# P2N-002.net
KiCad netlist of a schematic drawn in EAGLE
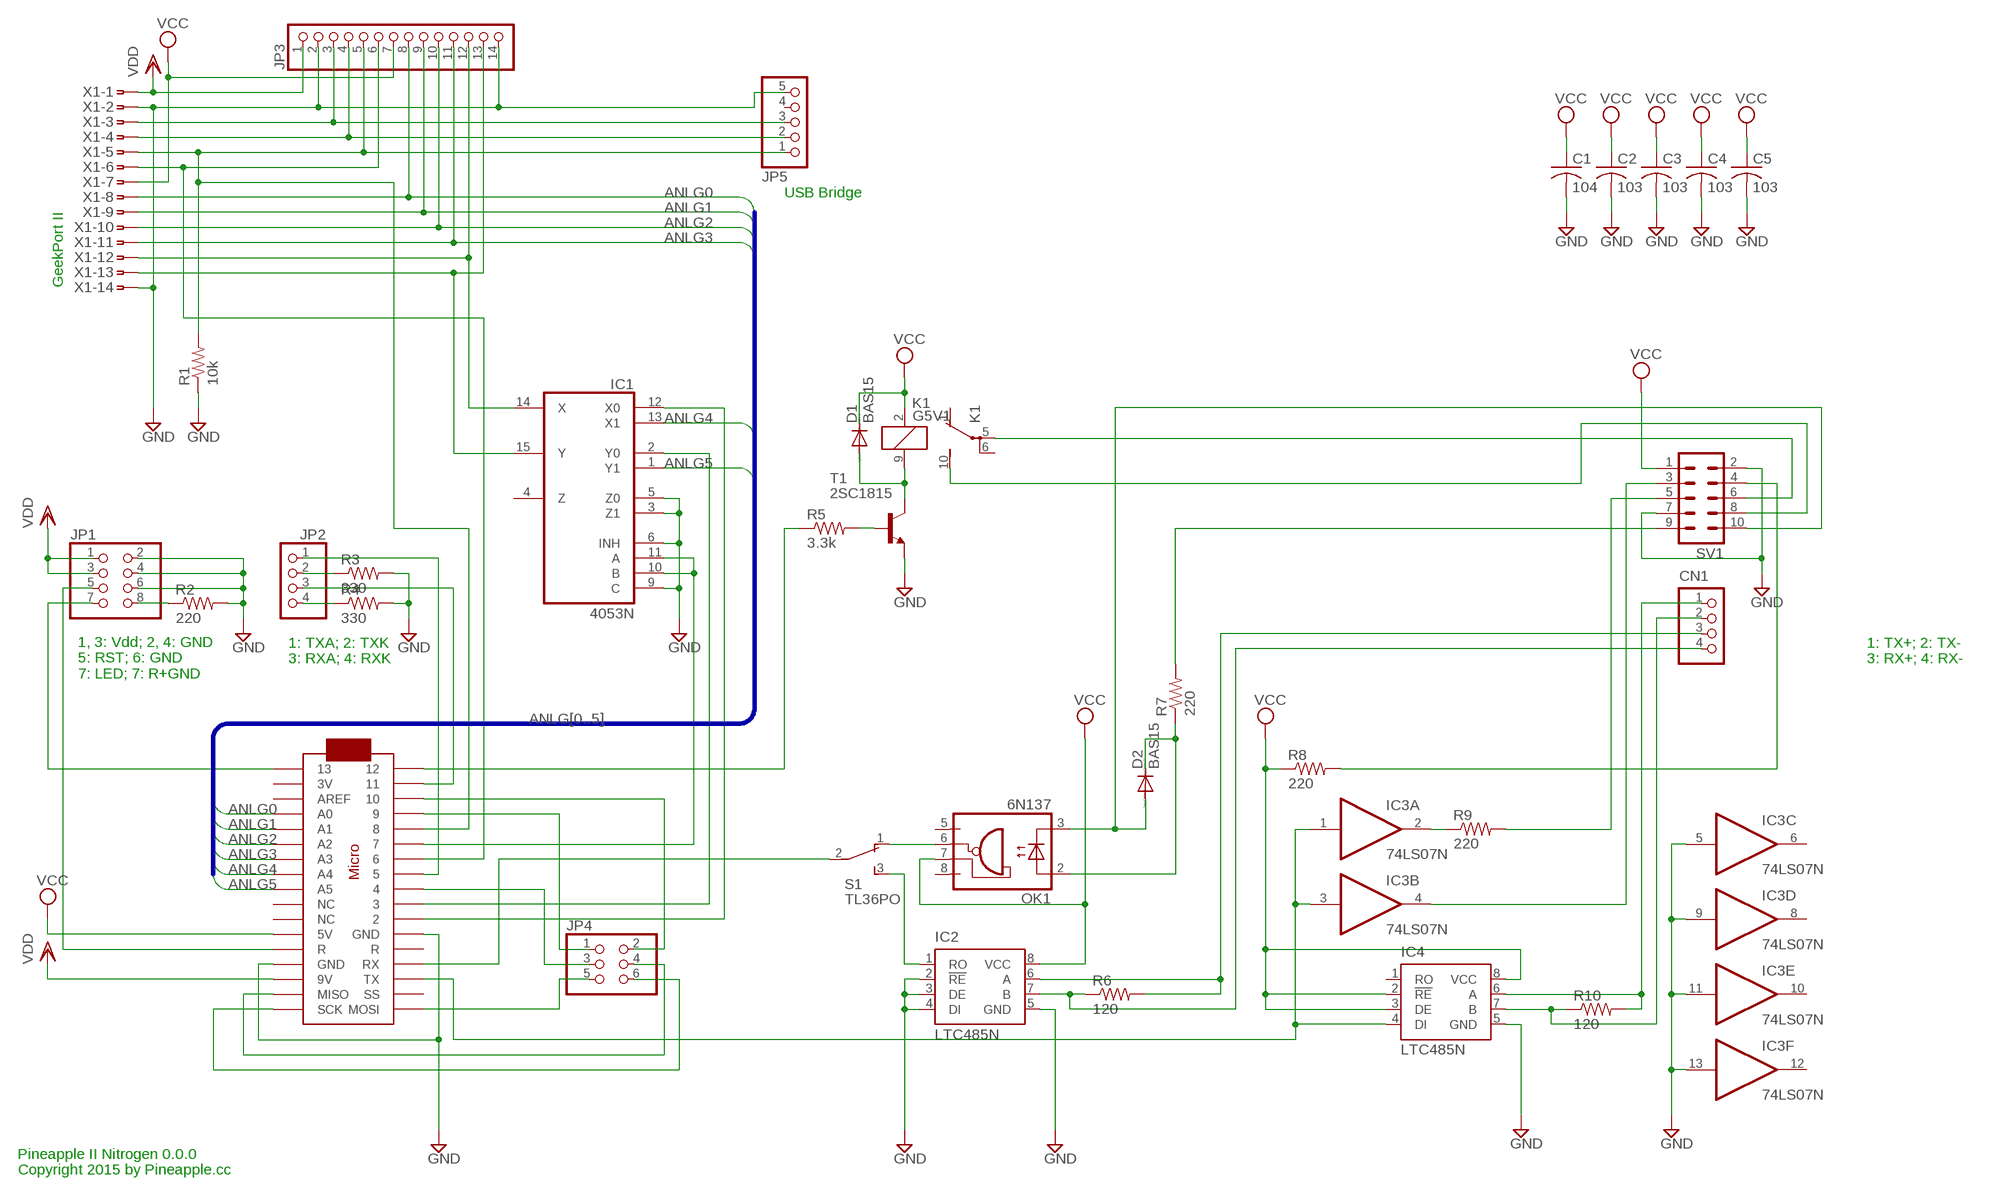
[diagram p0: schematic, sheet 1]

(export (version "E")
  (design (tool "Eeschema 10.0.6"))
  (components
    (comp (ref "C1")
      (value "104")
      (footprint "eagle-import:C025-025X050")
      (libsource (lib "eagle-import") (part "C-US025-025X050"))
    )
    (comp (ref "C2")
      (value "103")
      (footprint "eagle-import:C025-025X050")
      (libsource (lib "eagle-import") (part "C-US025-025X050"))
    )
    (comp (ref "C3")
      (value "103")
      (footprint "eagle-import:C025-025X050")
      (libsource (lib "eagle-import") (part "C-US025-025X050"))
    )
    (comp (ref "C4")
      (value "103")
      (footprint "eagle-import:C025-025X050")
      (libsource (lib "eagle-import") (part "C-US025-025X050"))
    )
    (comp (ref "C5")
      (value "103")
      (footprint "eagle-import:C025-025X050")
      (libsource (lib "eagle-import") (part "C-US025-025X050"))
    )
    (comp (ref "CN1")
      (value "S4B-PH-K-S")
      (footprint "eagle-import:S4B-PH-K-S")
      (libsource (lib "eagle-import") (part "S4B-PH-K-S"))
    )
    (comp (ref "D1")
      (value "BAS15")
      (footprint "eagle-import:DO34-7")
      (libsource (lib "eagle-import") (part "BAS15"))
    )
    (comp (ref "D2")
      (value "BAS15")
      (footprint "eagle-import:DO34-7")
      (libsource (lib "eagle-import") (part "BAS15"))
    )
    (comp (ref "IC1")
      (value "4053N")
      (footprint "eagle-import:DIL16")
      (libsource (lib "eagle-import") (part "4053N"))
    )
    (comp (ref "IC2")
      (value "LTC485N")
      (footprint "eagle-import:DIL08")
      (libsource (lib "eagle-import") (part "LTC485N"))
    )
    (comp (ref "IC3")
      (value "74LS07N")
      (footprint "eagle-import:DIL14")
      (libsource (lib "eagle-import") (part "7407NLS"))
    )
    (comp (ref "IC4")
      (value "LTC485N")
      (footprint "eagle-import:DIL08")
      (libsource (lib "eagle-import") (part "LTC485N"))
    )
    (comp (ref "JP1")
      (value "PINHD-2X4")
      (footprint "eagle-import:2X04")
      (libsource (lib "eagle-import") (part "PINHD-2X4"))
    )
    (comp (ref "JP2")
      (value "PINHD-1X4")
      (footprint "eagle-import:1X04")
      (libsource (lib "eagle-import") (part "PINHD-1X4"))
    )
    (comp (ref "JP3")
      (value "PINHD-1X14")
      (footprint "eagle-import:1X14")
      (libsource (lib "eagle-import") (part "PINHD-1X14"))
    )
    (comp (ref "JP4")
      (value "PINHD-2X3")
      (footprint "eagle-import:2X03")
      (libsource (lib "eagle-import") (part "PINHD-2X3"))
    )
    (comp (ref "JP5")
      (value "PINHD-1X5/90")
      (footprint "eagle-import:1X05_90")
      (libsource (lib "eagle-import") (part "PINHD-1X5/90"))
    )
    (comp (ref "K1")
      (value "G5V1")
      (footprint "eagle-import:G5V1")
      (fields (field (name "MPN") "G5V-1-DC24"))
      (libsource (lib "eagle-import") (part "G5V1"))
    )
    (comp (ref "MC1")
      (value "ARDUINOMICRO")
      (footprint "eagle-import:ARDUINOMICRO")
      (libsource (lib "eagle-import") (part "ARDUINOMICRO"))
    )
    (comp (ref "OK1")
      (value "6N137")
      (footprint "eagle-import:DIL08")
      (libsource (lib "eagle-import") (part "6N137"))
    )
    (comp (ref "R1")
      (value "10k")
      (footprint "eagle-import:0204_5")
      (libsource (lib "eagle-import") (part "R-US_0204/5"))
    )
    (comp (ref "R2")
      (value "220")
      (footprint "eagle-import:0204_5")
      (libsource (lib "eagle-import") (part "R-US_0204/5"))
    )
    (comp (ref "R3")
      (value "330")
      (footprint "eagle-import:0204_5")
      (libsource (lib "eagle-import") (part "R-US_0204/5"))
    )
    (comp (ref "R4")
      (value "330")
      (footprint "eagle-import:0204_5")
      (libsource (lib "eagle-import") (part "R-US_0204/5"))
    )
    (comp (ref "R5")
      (value "3.3k")
      (footprint "eagle-import:0204_5")
      (libsource (lib "eagle-import") (part "R-US_0204/5"))
    )
    (comp (ref "R6")
      (value "120")
      (footprint "eagle-import:0204_5")
      (libsource (lib "eagle-import") (part "R-US_0204/5"))
    )
    (comp (ref "R7")
      (value "220")
      (footprint "eagle-import:0204_5")
      (libsource (lib "eagle-import") (part "R-US_0204/5"))
    )
    (comp (ref "R8")
      (value "220")
      (footprint "eagle-import:0204_5")
      (libsource (lib "eagle-import") (part "R-US_0204/5"))
    )
    (comp (ref "R9")
      (value "220")
      (footprint "eagle-import:0204_5")
      (libsource (lib "eagle-import") (part "R-US_0204/5"))
    )
    (comp (ref "R10")
      (value "120")
      (footprint "eagle-import:0204_5")
      (libsource (lib "eagle-import") (part "R-US_0204/5"))
    )
    (comp (ref "S1")
      (value "TL36PO")
      (footprint "eagle-import:TL3XPO")
      (libsource (lib "eagle-import") (part "TL36PO"))
    )
    (comp (ref "SV1")
      (value "ML10L")
      (footprint "eagle-import:ML10L")
      (libsource (lib "eagle-import") (part "ML10L"))
    )
    (comp (ref "T1")
      (value "2SC1815")
      (footprint "eagle-import:TO92-ECB")
      (libsource (lib "eagle-import") (part "2SC1815"))
    )
    (comp (ref "X1")
      (value "HIROSE-DXLM")
      (footprint "eagle-import:HIROSE-DXLM")
      (libsource (lib "eagle-import") (part "HIROSE-DXLM"))
    )
  )
  (nets
    (net (code "1") (name "/ANLG0") (class "Default")
      (node (ref "JP3") (pin "8") (pinfunction "8_8") (pintype "passive"))
      (node (ref "MC1") (pin "P$31") (pinfunction "A0_P$31") (pintype "bidirectional"))
      (node (ref "X1") (pin "8") (pinfunction "1_8") (pintype "passive"))
    )
    (net (code "2") (name "/ANLG1") (class "Default")
      (node (ref "JP3") (pin "9") (pinfunction "9_9") (pintype "passive"))
      (node (ref "MC1") (pin "P$30") (pinfunction "A1_P$30") (pintype "bidirectional"))
      (node (ref "X1") (pin "9") (pinfunction "1_9") (pintype "passive"))
    )
    (net (code "3") (name "/ANLG2") (class "Default")
      (node (ref "JP3") (pin "10") (pinfunction "10_10") (pintype "passive"))
      (node (ref "MC1") (pin "P$29") (pinfunction "A2_P$29") (pintype "bidirectional"))
      (node (ref "X1") (pin "10") (pinfunction "1_10") (pintype "passive"))
    )
    (net (code "4") (name "/ANLG3") (class "Default")
      (node (ref "JP3") (pin "11") (pinfunction "11_11") (pintype "passive"))
      (node (ref "MC1") (pin "P$28") (pinfunction "A3_P$28") (pintype "bidirectional"))
      (node (ref "X1") (pin "11") (pinfunction "1_11") (pintype "passive"))
    )
    (net (code "5") (name "/ANLG4") (class "Default")
      (node (ref "IC1") (pin "13") (pinfunction "X1_13") (pintype "bidirectional"))
      (node (ref "MC1") (pin "P$27") (pinfunction "A4_P$27") (pintype "bidirectional"))
    )
    (net (code "6") (name "/ANLG5") (class "Default")
      (node (ref "IC1") (pin "1") (pinfunction "Y1_1") (pintype "bidirectional"))
      (node (ref "MC1") (pin "P$26") (pinfunction "A5_P$26") (pintype "bidirectional"))
    )
    (net (code "8") (name "GND") (class "Default")
      (node (ref "C1") (pin "2") (pinfunction "2_2") (pintype "passive"))
      (node (ref "C2") (pin "2") (pinfunction "2_2") (pintype "passive"))
      (node (ref "C3") (pin "2") (pinfunction "2_2") (pintype "passive"))
      (node (ref "C4") (pin "2") (pinfunction "2_2") (pintype "passive"))
      (node (ref "C5") (pin "2") (pinfunction "2_2") (pintype "passive"))
      (node (ref "IC1") (pin "3") (pinfunction "Z1_3") (pintype "bidirectional"))
      (node (ref "IC1") (pin "5") (pinfunction "Z0_5") (pintype "bidirectional"))
      (node (ref "IC1") (pin "6") (pinfunction "INH_6") (pintype "input"))
      (node (ref "IC1") (pin "9") (pinfunction "C_9") (pintype "input"))
      (node (ref "IC2") (pin "2") (pinfunction "~{RE}_2") (pintype "input"))
      (node (ref "IC2") (pin "3") (pinfunction "DE_3") (pintype "input"))
      (node (ref "IC2") (pin "4") (pinfunction "DI_4") (pintype "input"))
      (node (ref "IC2") (pin "5") (pinfunction "GND_5") (pintype "input"))
      (node (ref "IC3") (pin "11") (pinfunction "I_11") (pintype "input"))
      (node (ref "IC3") (pin "13") (pinfunction "I_13") (pintype "input"))
      (node (ref "IC3") (pin "5") (pinfunction "I_5") (pintype "input"))
      (node (ref "IC3") (pin "9") (pinfunction "I_9") (pintype "input"))
      (node (ref "IC4") (pin "5") (pinfunction "GND_5") (pintype "input"))
      (node (ref "JP1") (pin "2") (pinfunction "2_2") (pintype "passive"))
      (node (ref "JP1") (pin "4") (pinfunction "4_4") (pintype "passive"))
      (node (ref "JP1") (pin "6") (pinfunction "6_6") (pintype "passive"))
      (node (ref "JP3") (pin "14") (pinfunction "14_14") (pintype "passive"))
      (node (ref "JP3") (pin "2") (pinfunction "2_2") (pintype "passive"))
      (node (ref "JP5") (pin "5") (pinfunction "5_5") (pintype "passive"))
      (node (ref "MC1") (pin "P$12") (pinfunction "GND_P$12") (pintype "bidirectional"))
      (node (ref "MC1") (pin "P$21") (pinfunction "GND_P$21") (pintype "bidirectional"))
      (node (ref "R1") (pin "1") (pinfunction "1_1") (pintype "passive"))
      (node (ref "R2") (pin "2") (pinfunction "2_2") (pintype "passive"))
      (node (ref "R3") (pin "2") (pinfunction "2_2") (pintype "passive"))
      (node (ref "R4") (pin "2") (pinfunction "2_2") (pintype "passive"))
      (node (ref "SV1") (pin "2") (pinfunction "2_2") (pintype "passive"))
      (node (ref "SV1") (pin "7") (pinfunction "7_7") (pintype "passive"))
      (node (ref "T1") (pin "E") (pinfunction "E_E") (pintype "passive"))
      (node (ref "X1") (pin "14") (pinfunction "1_14") (pintype "passive"))
      (node (ref "X1") (pin "2") (pinfunction "1_2") (pintype "passive"))
    )
    (net (code "9") (name "Net-(IC1A-A)") (class "Default")
      (node (ref "IC1") (pin "10") (pinfunction "B_10") (pintype "input"))
      (node (ref "IC1") (pin "11") (pinfunction "A_11") (pintype "input"))
      (node (ref "MC1") (pin "P$6") (pinfunction "7_P$6") (pintype "bidirectional"))
    )
    (net (code "10") (name "Net-(IC1A-X)") (class "Default")
      (node (ref "IC1") (pin "14") (pinfunction "X_14") (pintype "bidirectional"))
      (node (ref "JP3") (pin "12") (pinfunction "12_12") (pintype "passive"))
      (node (ref "X1") (pin "12") (pinfunction "1_12") (pintype "passive"))
    )
    (net (code "11") (name "Net-(IC1A-X0)") (class "Default")
      (node (ref "IC1") (pin "12") (pinfunction "X0_12") (pintype "bidirectional"))
      (node (ref "MC1") (pin "P$11") (pinfunction "2_P$11") (pintype "bidirectional"))
    )
    (net (code "12") (name "Net-(IC1A-Y)") (class "Default")
      (node (ref "IC1") (pin "15") (pinfunction "Y_15") (pintype "bidirectional"))
      (node (ref "JP3") (pin "13") (pinfunction "13_13") (pintype "passive"))
      (node (ref "X1") (pin "13") (pinfunction "1_13") (pintype "passive"))
    )
    (net (code "13") (name "Net-(IC1A-Y0)") (class "Default")
      (node (ref "IC1") (pin "2") (pinfunction "Y0_2") (pintype "bidirectional"))
      (node (ref "MC1") (pin "P$10") (pinfunction "3_P$10") (pintype "bidirectional"))
    )
    (net (code "14") (name "Net-(IC2-A)") (class "Default")
      (node (ref "CN1") (pin "3") (pinfunction "3_3") (pintype "passive"))
      (node (ref "IC2") (pin "6") (pinfunction "A_6") (pintype "bidirectional"))
      (node (ref "R6") (pin "2") (pinfunction "2_2") (pintype "passive"))
    )
    (net (code "15") (name "Net-(IC2-B)") (class "Default")
      (node (ref "CN1") (pin "4") (pinfunction "4_4") (pintype "passive"))
      (node (ref "IC2") (pin "7") (pinfunction "B_7") (pintype "bidirectional"))
      (node (ref "R6") (pin "1") (pinfunction "1_1") (pintype "passive"))
    )
    (net (code "16") (name "Net-(IC2-RO)") (class "Default")
      (node (ref "IC2") (pin "1") (pinfunction "RO_1") (pintype "output"))
      (node (ref "S1") (pin "3") (pinfunction "S_3") (pintype "passive"))
    )
    (net (code "17") (name "Net-(IC3A-I)") (class "Default")
      (node (ref "IC3") (pin "1") (pinfunction "I_1") (pintype "input"))
      (node (ref "IC3") (pin "3") (pinfunction "I_3") (pintype "input"))
      (node (ref "IC4") (pin "4") (pinfunction "DI_4") (pintype "input"))
      (node (ref "MC1") (pin "P$15") (pinfunction "TX_P$15") (pintype "bidirectional"))
    )
    (net (code "18") (name "Net-(IC3A-O)") (class "Default")
      (node (ref "IC3") (pin "2") (pinfunction "O_2") (pintype "open_collector"))
      (node (ref "R9") (pin "1") (pinfunction "1_1") (pintype "passive"))
    )
    (net (code "19") (name "Net-(IC3B-O)") (class "Default")
      (node (ref "IC3") (pin "4") (pinfunction "O_4") (pintype "open_collector"))
      (node (ref "SV1") (pin "3") (pinfunction "3_3") (pintype "passive"))
    )
    (net (code "20") (name "Net-(IC4-A)") (class "Default")
      (node (ref "CN1") (pin "1") (pinfunction "1_1") (pintype "passive"))
      (node (ref "IC4") (pin "6") (pinfunction "A_6") (pintype "bidirectional"))
      (node (ref "R10") (pin "2") (pinfunction "2_2") (pintype "passive"))
    )
    (net (code "21") (name "Net-(IC4-B)") (class "Default")
      (node (ref "CN1") (pin "2") (pinfunction "2_2") (pintype "passive"))
      (node (ref "IC4") (pin "7") (pinfunction "B_7") (pintype "bidirectional"))
      (node (ref "R10") (pin "1") (pinfunction "1_1") (pintype "passive"))
    )
    (net (code "22") (name "Net-(JP1-Pad5)") (class "Default")
      (node (ref "JP1") (pin "5") (pinfunction "5_5") (pintype "passive"))
      (node (ref "MC1") (pin "P$13") (pinfunction "R_P$13") (pintype "bidirectional"))
    )
    (net (code "23") (name "Net-(JP1-Pad8)") (class "Default")
      (node (ref "JP1") (pin "8") (pinfunction "8_8") (pintype "passive"))
      (node (ref "R2") (pin "1") (pinfunction "1_1") (pintype "passive"))
    )
    (net (code "24") (name "Net-(JP2-Pad2)") (class "Default")
      (node (ref "JP2") (pin "2") (pinfunction "2_2") (pintype "passive"))
      (node (ref "R3") (pin "1") (pinfunction "1_1") (pintype "passive"))
    )
    (net (code "25") (name "Net-(JP2-Pad4)") (class "Default")
      (node (ref "JP2") (pin "4") (pinfunction "4_4") (pintype "passive"))
      (node (ref "R4") (pin "1") (pinfunction "1_1") (pintype "passive"))
    )
    (net (code "26") (name "Net-(K1A-2)") (class "Default")
      (node (ref "D1") (pin "A") (pinfunction "A_A") (pintype "passive"))
      (node (ref "K1") (pin "9") (pinfunction "2_9") (pintype "passive"))
      (node (ref "T1") (pin "C") (pinfunction "C_C") (pintype "passive"))
    )
    (net (code "27") (name "Net-(K1B-P-Pad5)") (class "Default")
      (node (ref "K1") (pin "5") (pinfunction "P_5") (pintype "passive"))
      (node (ref "SV1") (pin "6") (pinfunction "6_6") (pintype "passive"))
    )
    (net (code "28") (name "Net-(K1B-S)") (class "Default")
      (node (ref "K1") (pin "10") (pinfunction "S_10") (pintype "passive"))
      (node (ref "SV1") (pin "8") (pinfunction "8_8") (pintype "passive"))
    )
    (net (code "29") (name "Net-(MC1-4)") (class "Default")
      (node (ref "JP4") (pin "3") (pinfunction "3_3") (pintype "passive"))
      (node (ref "MC1") (pin "P$9") (pinfunction "4_P$9") (pintype "bidirectional"))
    )
    (net (code "30") (name "Net-(MC1-5)") (class "Default")
      (node (ref "JP2") (pin "1") (pinfunction "1_1") (pintype "passive"))
      (node (ref "MC1") (pin "P$8") (pinfunction "5_P$8") (pintype "bidirectional"))
    )
    (net (code "31") (name "Net-(MC1-6)") (class "Default")
      (node (ref "JP3") (pin "6") (pinfunction "6_6") (pintype "passive"))
      (node (ref "MC1") (pin "P$7") (pinfunction "6_P$7") (pintype "bidirectional"))
      (node (ref "X1") (pin "6") (pinfunction "1_6") (pintype "passive"))
    )
    (net (code "32") (name "Net-(MC1-8)") (class "Default")
      (node (ref "JP3") (pin "5") (pinfunction "5_5") (pintype "passive"))
      (node (ref "JP5") (pin "1") (pinfunction "1_1") (pintype "passive"))
      (node (ref "MC1") (pin "P$5") (pinfunction "8_P$5") (pintype "bidirectional"))
      (node (ref "R1") (pin "2") (pinfunction "2_2") (pintype "passive"))
      (node (ref "X1") (pin "5") (pinfunction "1_5") (pintype "passive"))
    )
    (net (code "33") (name "Net-(MC1-9)") (class "Default")
      (node (ref "JP4") (pin "1") (pinfunction "1_1") (pintype "passive"))
      (node (ref "MC1") (pin "P$4") (pinfunction "9_P$4") (pintype "bidirectional"))
    )
    (net (code "34") (name "Net-(MC1-10)") (class "Default")
      (node (ref "JP4") (pin "2") (pinfunction "2_2") (pintype "passive"))
      (node (ref "MC1") (pin "P$3") (pinfunction "10_P$3") (pintype "bidirectional"))
    )
    (net (code "35") (name "Net-(MC1-11)") (class "Default")
      (node (ref "JP2") (pin "3") (pinfunction "3_3") (pintype "passive"))
      (node (ref "MC1") (pin "P$2") (pinfunction "11_P$2") (pintype "bidirectional"))
    )
    (net (code "36") (name "Net-(MC1-12)") (class "Default")
      (node (ref "MC1") (pin "P$1") (pinfunction "12_P$1") (pintype "bidirectional"))
      (node (ref "R5") (pin "1") (pinfunction "1_1") (pintype "passive"))
    )
    (net (code "37") (name "Net-(MC1-13)") (class "Default")
      (node (ref "JP1") (pin "7") (pinfunction "7_7") (pintype "passive"))
      (node (ref "MC1") (pin "P$34") (pinfunction "13_P$34") (pintype "bidirectional"))
    )
    (net (code "38") (name "Net-(MC1-MISO)") (class "Default")
      (node (ref "JP4") (pin "4") (pinfunction "4_4") (pintype "passive"))
      (node (ref "MC1") (pin "P$19") (pinfunction "MISO_P$19") (pintype "bidirectional"))
    )
    (net (code "39") (name "Net-(MC1-MOSI)") (class "Default")
      (node (ref "JP4") (pin "5") (pinfunction "5_5") (pintype "passive"))
      (node (ref "MC1") (pin "P$17") (pinfunction "MOSI_P$17") (pintype "bidirectional"))
    )
    (net (code "40") (name "Net-(MC1-RX)") (class "Default")
      (node (ref "MC1") (pin "P$14") (pinfunction "RX_P$14") (pintype "bidirectional"))
      (node (ref "S1") (pin "2") (pinfunction "P_2") (pintype "passive"))
    )
    (net (code "41") (name "Net-(MC1-SCK)") (class "Default")
      (node (ref "JP4") (pin "6") (pinfunction "6_6") (pintype "passive"))
      (node (ref "MC1") (pin "P$18") (pinfunction "SCK_P$18") (pintype "bidirectional"))
    )
    (net (code "42") (name "Net-(OK1-A)") (class "Default")
      (node (ref "D2") (pin "C") (pinfunction "C_C") (pintype "passive"))
      (node (ref "OK1") (pin "2") (pinfunction "A_2") (pintype "passive"))
      (node (ref "R7") (pin "1") (pinfunction "1_1") (pintype "passive"))
    )
    (net (code "43") (name "Net-(OK1-C)") (class "Default")
      (node (ref "D2") (pin "A") (pinfunction "A_A") (pintype "passive"))
      (node (ref "OK1") (pin "3") (pinfunction "C_3") (pintype "passive"))
      (node (ref "SV1") (pin "10") (pinfunction "10_10") (pintype "passive"))
    )
    (net (code "44") (name "Net-(OK1-VO)") (class "Default")
      (node (ref "OK1") (pin "6") (pinfunction "VO_6") (pintype "passive"))
      (node (ref "S1") (pin "1") (pinfunction "O_1") (pintype "passive"))
    )
    (net (code "45") (name "Net-(R5-Pad2)") (class "Default")
      (node (ref "R5") (pin "2") (pinfunction "2_2") (pintype "passive"))
      (node (ref "T1") (pin "B") (pinfunction "B_B") (pintype "passive"))
    )
    (net (code "46") (name "Net-(R7-Pad2)") (class "Default")
      (node (ref "R7") (pin "2") (pinfunction "2_2") (pintype "passive"))
      (node (ref "SV1") (pin "9") (pinfunction "9_9") (pintype "passive"))
    )
    (net (code "47") (name "Net-(R8-Pad2)") (class "Default")
      (node (ref "R8") (pin "2") (pinfunction "2_2") (pintype "passive"))
      (node (ref "SV1") (pin "4") (pinfunction "4_4") (pintype "passive"))
    )
    (net (code "48") (name "Net-(R9-Pad2)") (class "Default")
      (node (ref "R9") (pin "2") (pinfunction "2_2") (pintype "passive"))
      (node (ref "SV1") (pin "5") (pinfunction "5_5") (pintype "passive"))
    )
    (net (code "49") (name "Net-(X1H-1)") (class "Default")
      (node (ref "JP3") (pin "3") (pinfunction "3_3") (pintype "passive"))
      (node (ref "JP5") (pin "3") (pinfunction "3_3") (pintype "passive"))
      (node (ref "X1") (pin "3") (pinfunction "1_3") (pintype "passive"))
    )
    (net (code "50") (name "Net-(X1I-1)") (class "Default")
      (node (ref "JP3") (pin "4") (pinfunction "4_4") (pintype "passive"))
      (node (ref "JP5") (pin "2") (pinfunction "2_2") (pintype "passive"))
      (node (ref "X1") (pin "4") (pinfunction "1_4") (pintype "passive"))
    )
    (net (code "51") (name "VCC") (class "Default")
      (node (ref "C1") (pin "1") (pinfunction "1_1") (pintype "passive"))
      (node (ref "C2") (pin "1") (pinfunction "1_1") (pintype "passive"))
      (node (ref "C3") (pin "1") (pinfunction "1_1") (pintype "passive"))
      (node (ref "C4") (pin "1") (pinfunction "1_1") (pintype "passive"))
      (node (ref "C5") (pin "1") (pinfunction "1_1") (pintype "passive"))
      (node (ref "D1") (pin "C") (pinfunction "C_C") (pintype "passive"))
      (node (ref "IC2") (pin "8") (pinfunction "VCC_8") (pintype "input"))
      (node (ref "IC4") (pin "2") (pinfunction "~{RE}_2") (pintype "input"))
      (node (ref "IC4") (pin "3") (pinfunction "DE_3") (pintype "input"))
      (node (ref "IC4") (pin "8") (pinfunction "VCC_8") (pintype "input"))
      (node (ref "JP3") (pin "7") (pinfunction "7_7") (pintype "passive"))
      (node (ref "K1") (pin "2") (pinfunction "1_2") (pintype "passive"))
      (node (ref "MC1") (pin "P$23") (pinfunction "5V_P$23") (pintype "bidirectional"))
      (node (ref "OK1") (pin "7") (pinfunction "VE_7") (pintype "passive"))
      (node (ref "R8") (pin "1") (pinfunction "1_1") (pintype "passive"))
      (node (ref "SV1") (pin "1") (pinfunction "1_1") (pintype "passive"))
      (node (ref "X1") (pin "7") (pinfunction "1_7") (pintype "passive"))
    )
    (net (code "52") (name "VDD") (class "Default")
      (node (ref "JP1") (pin "1") (pinfunction "1_1") (pintype "passive"))
      (node (ref "JP1") (pin "3") (pinfunction "3_3") (pintype "passive"))
      (node (ref "JP3") (pin "1") (pinfunction "1_1") (pintype "passive"))
      (node (ref "MC1") (pin "P$20") (pinfunction "9V_P$20") (pintype "bidirectional"))
      (node (ref "X1") (pin "1") (pinfunction "1_1") (pintype "passive"))
    )
    (net (code "53") (name "unconnected-(IC1A-Z-Pad4)") (class "Default")
      (node (ref "IC1") (pin "4") (pinfunction "Z_4") (pintype "bidirectional"))
    )
    (net (code "54") (name "unconnected-(IC3C-O-Pad6)") (class "Default")
      (node (ref "IC3") (pin "6") (pinfunction "O_6") (pintype "open_collector"))
    )
    (net (code "55") (name "unconnected-(IC3D-O-Pad8)") (class "Default")
      (node (ref "IC3") (pin "8") (pinfunction "O_8") (pintype "open_collector"))
    )
    (net (code "56") (name "unconnected-(IC3E-O-Pad10)") (class "Default")
      (node (ref "IC3") (pin "10") (pinfunction "O_10") (pintype "open_collector"))
    )
    (net (code "57") (name "unconnected-(IC3F-O-Pad12)") (class "Default")
      (node (ref "IC3") (pin "12") (pinfunction "O_12") (pintype "open_collector"))
    )
    (net (code "58") (name "unconnected-(IC4-RO-Pad1)") (class "Default")
      (node (ref "IC4") (pin "1") (pinfunction "RO_1") (pintype "output"))
    )
    (net (code "59") (name "unconnected-(JP5-Pad4)") (class "Default")
      (node (ref "JP5") (pin "4") (pinfunction "4_4") (pintype "passive"))
    )
    (net (code "60") (name "unconnected-(K1B-O-Pad1)") (class "Default")
      (node (ref "K1") (pin "1") (pinfunction "O_1") (pintype "passive"))
    )
    (net (code "61") (name "unconnected-(K1B-P-Pad6)") (class "Default")
      (node (ref "K1") (pin "6") (pinfunction "P_6") (pintype "passive"))
    )
    (net (code "62") (name "unconnected-(MC1-3V-PadP$33)") (class "Default")
      (node (ref "MC1") (pin "P$33") (pinfunction "3V_P$33") (pintype "bidirectional"))
    )
    (net (code "63") (name "unconnected-(MC1-AREF-PadP$32)") (class "Default")
      (node (ref "MC1") (pin "P$32") (pinfunction "AREF_P$32") (pintype "bidirectional"))
    )
    (net (code "64") (name "unconnected-(MC1-NC-PadP$24)") (class "Default")
      (node (ref "MC1") (pin "P$24") (pinfunction "NC_P$24") (pintype "bidirectional"))
    )
    (net (code "65") (name "unconnected-(MC1-NC-PadP$25)") (class "Default")
      (node (ref "MC1") (pin "P$25") (pinfunction "NC_P$25") (pintype "bidirectional"))
    )
    (net (code "66") (name "unconnected-(MC1-R-PadP$22)") (class "Default")
      (node (ref "MC1") (pin "P$22") (pinfunction "R_P$22") (pintype "bidirectional"))
    )
    (net (code "67") (name "unconnected-(MC1-SS-PadP$16)") (class "Default")
      (node (ref "MC1") (pin "P$16") (pinfunction "SS_P$16") (pintype "bidirectional"))
    )
    (net (code "68") (name "unconnected-(OK1-GND-Pad5)") (class "Default")
      (node (ref "OK1") (pin "5") (pinfunction "GND_5") (pintype "passive"))
    )
    (net (code "69") (name "unconnected-(OK1-VCC-Pad8)") (class "Default")
      (node (ref "OK1") (pin "8") (pinfunction "VCC_8") (pintype "passive"))
    )
  )
)
